# Variable_PWM.net
KiCad netlist of a schematic drawn in EAGLE
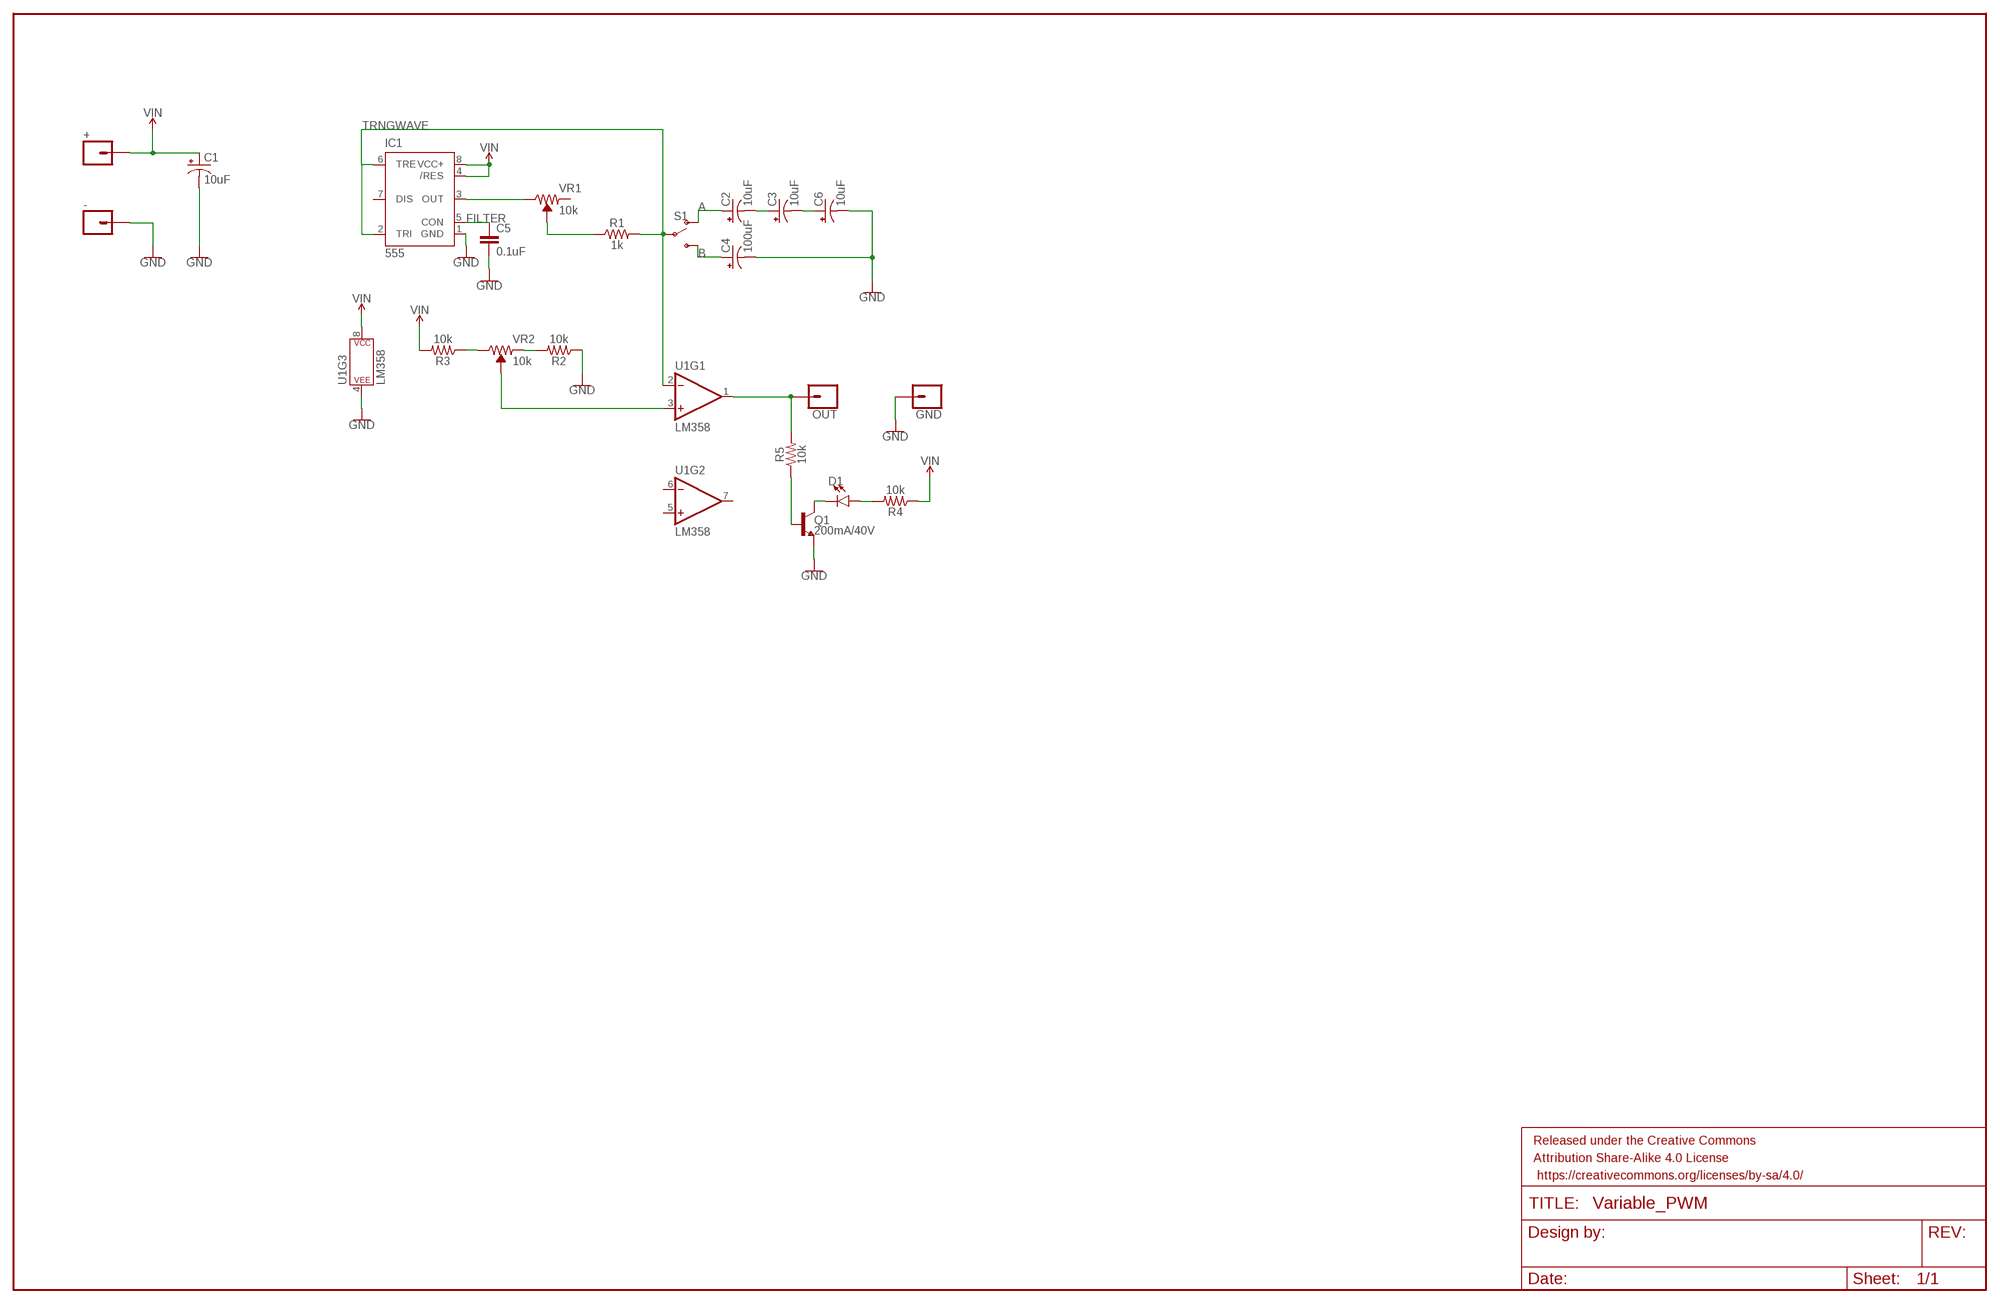
[diagram p0: schematic, sheet 1]

(export (version "E")
  (design (tool "Eeschema 10.0.6"))
  (components
    (comp (ref "+")
      (value "CONN_01")
      (footprint "eagle-import:1X01")
      (libsource (lib "eagle-import") (part "CONN_01"))
    )
    (comp (ref "-")
      (value "CONN_01")
      (footprint "eagle-import:1X01")
      (libsource (lib "eagle-import") (part "CONN_01"))
    )
    (comp (ref "C1")
      (value "10uF")
      (footprint "eagle-import:CPOL-RADIAL-2.5MM-5MM")
      (libsource (lib "eagle-import") (part "10UF-POLAR-RADIAL-2.5MM-25V-20%"))
    )
    (comp (ref "C2")
      (value "10uF")
      (footprint "eagle-import:CPOL-RADIAL-2.5MM-5MM")
      (libsource (lib "eagle-import") (part "10UF-POLAR-RADIAL-2.5MM-25V-20%"))
    )
    (comp (ref "C3")
      (value "10uF")
      (footprint "eagle-import:CPOL-RADIAL-2.5MM-5MM")
      (libsource (lib "eagle-import") (part "10UF-POLAR-RADIAL-2.5MM-25V-20%"))
    )
    (comp (ref "C4")
      (value "100uF")
      (footprint "eagle-import:CPOL-RADIAL-2.5MM-6.5MM")
      (libsource (lib "eagle-import") (part "100UF-POLAR-RADIAL-2.5MM-25V-20%"))
    )
    (comp (ref "C5")
      (value "0.1uF")
      (footprint "eagle-import:CAP-PTH-SMALL-KIT")
      (libsource (lib "eagle-import") (part "0.1UF-KIT-EZ-50V-20%"))
    )
    (comp (ref "C6")
      (value "10uF")
      (footprint "eagle-import:CPOL-RADIAL-2.5MM-5MM")
      (libsource (lib "eagle-import") (part "10UF-POLAR-RADIAL-2.5MM-25V-20%"))
    )
    (comp (ref "D1")
      (value "LED5MM")
      (footprint "eagle-import:LED_5MM")
      (libsource (lib "eagle-import") (part "LED5MM"))
    )
    (comp (ref "FRAME1")
      (value "FRAME-LEDGERNO_FOOTPRINT")
      (footprint "eagle-import:DUMMY")
      (libsource (lib "eagle-import") (part "FRAME-LEDGERNO_FOOTPRINT"))
    )
    (comp (ref "GND")
      (value "CONN_01")
      (footprint "eagle-import:1X01")
      (libsource (lib "eagle-import") (part "CONN_01"))
    )
    (comp (ref "IC1")
      (value "555")
      (footprint "eagle-import:DIP08")
      (libsource (lib "eagle-import") (part "555P"))
    )
    (comp (ref "OUT")
      (value "CONN_01")
      (footprint "eagle-import:1X01")
      (libsource (lib "eagle-import") (part "CONN_01"))
    )
    (comp (ref "Q1")
      (value "200mA/40V")
      (footprint "eagle-import:TO-92")
      (libsource (lib "eagle-import") (part "TRANS_NPN-2N3904"))
    )
    (comp (ref "R1")
      (value "1k")
      (footprint "eagle-import:AXIAL-0.3")
      (libsource (lib "eagle-import") (part "1KOHM-HORIZ-1/4W-1%"))
    )
    (comp (ref "R2")
      (value "10k")
      (footprint "eagle-import:AXIAL-0.3")
      (libsource (lib "eagle-import") (part "10KOHM-HORIZ-1/4W-1%"))
    )
    (comp (ref "R3")
      (value "10k")
      (footprint "eagle-import:AXIAL-0.3")
      (libsource (lib "eagle-import") (part "10KOHM-HORIZ-1/4W-1%"))
    )
    (comp (ref "R4")
      (value "10k")
      (footprint "eagle-import:AXIAL-0.3")
      (libsource (lib "eagle-import") (part "10KOHM-HORIZ-1/4W-1%"))
    )
    (comp (ref "R5")
      (value "10k")
      (footprint "eagle-import:AXIAL-0.3")
      (libsource (lib "eagle-import") (part "10KOHM-HORIZ-1/4W-1%"))
    )
    (comp (ref "S1")
      (value "SWITCH-SPDT-PTH-11.6X4.0MM")
      (footprint "eagle-import:SWITCH_SPDT_PTH_11.6X4.0MM")
      (libsource (lib "eagle-import") (part "SWITCH-SPDT-PTH-11.6X4.0MM"))
    )
    (comp (ref "U1")
      (value "LM358")
      (footprint "eagle-import:DIP08")
      (libsource (lib "eagle-import") (part "LM358"))
    )
    (comp (ref "VR1")
      (value "10k")
      (footprint "eagle-import:TRIMPOT-PTH-3386U")
      (libsource (lib "eagle-import") (part "TRIMPOT-PTH-10MM-KNOB-1/2W-10%"))
    )
    (comp (ref "VR2")
      (value "10k")
      (footprint "eagle-import:TRIMPOT-PTH-3386U")
      (libsource (lib "eagle-import") (part "TRIMPOT-PTH-10MM-KNOB-1/2W-10%"))
    )
  )
  (nets
    (net (code "1") (name "/A") (class "Default")
      (node (ref "C2") (pin "1") (pinfunction "+_1") (pintype "passive"))
      (node (ref "S1") (pin "1") (pinfunction "O_1") (pintype "passive"))
    )
    (net (code "2") (name "/B") (class "Default")
      (node (ref "C4") (pin "1") (pinfunction "+_1") (pintype "passive"))
      (node (ref "S1") (pin "3") (pinfunction "S_3") (pintype "passive"))
    )
    (net (code "3") (name "/FILTER") (class "Default")
      (node (ref "C5") (pin "1") (pinfunction "1_1") (pintype "passive"))
      (node (ref "IC1") (pin "5") (pinfunction "CON_5") (pintype "input"))
    )
    (net (code "4") (name "/TRNGWAVE") (class "Default")
      (node (ref "IC1") (pin "2") (pinfunction "TRI_2") (pintype "input"))
      (node (ref "IC1") (pin "6") (pinfunction "TRE_6") (pintype "input"))
      (node (ref "R1") (pin "P$2") (pinfunction "2_P$2") (pintype "passive"))
      (node (ref "S1") (pin "2") (pinfunction "P_2") (pintype "passive"))
      (node (ref "U1") (pin "2") (pinfunction "-IN_2") (pintype "input"))
    )
    (net (code "5") (name "GND") (class "Default")
      (node (ref "-") (pin "1") (pinfunction "1_1") (pintype "passive"))
      (node (ref "C1") (pin "2") (pinfunction "-_2") (pintype "passive"))
      (node (ref "C4") (pin "2") (pinfunction "-_2") (pintype "passive"))
      (node (ref "C5") (pin "2") (pinfunction "2_2") (pintype "passive"))
      (node (ref "C6") (pin "2") (pinfunction "-_2") (pintype "passive"))
      (node (ref "GND") (pin "1") (pinfunction "1_1") (pintype "passive"))
      (node (ref "IC1") (pin "1") (pinfunction "GND_1") (pintype "power_in"))
      (node (ref "Q1") (pin "1") (pinfunction "E_1") (pintype "passive"))
      (node (ref "R2") (pin "P$1") (pinfunction "1_P$1") (pintype "passive"))
      (node (ref "U1") (pin "4") (pinfunction "P$V-_4") (pintype "bidirectional"))
    )
    (net (code "6") (name "Net-(C2--)") (class "Default")
      (node (ref "C2") (pin "2") (pinfunction "-_2") (pintype "passive"))
      (node (ref "C3") (pin "1") (pinfunction "+_1") (pintype "passive"))
    )
    (net (code "7") (name "Net-(C3--)") (class "Default")
      (node (ref "C3") (pin "2") (pinfunction "-_2") (pintype "passive"))
      (node (ref "C6") (pin "1") (pinfunction "+_1") (pintype "passive"))
    )
    (net (code "8") (name "Net-(D1-C)") (class "Default")
      (node (ref "D1") (pin "K") (pinfunction "C_K") (pintype "passive"))
      (node (ref "Q1") (pin "3") (pinfunction "C_3") (pintype "passive"))
    )
    (net (code "9") (name "Net-(IC1-OUT)") (class "Default")
      (node (ref "IC1") (pin "3") (pinfunction "OUT_3") (pintype "output"))
      (node (ref "VR1") (pin "3") (pinfunction "CW_3") (pintype "passive"))
    )
    (net (code "10") (name "Net-(Q1-B)") (class "Default")
      (node (ref "Q1") (pin "2") (pinfunction "B_2") (pintype "passive"))
      (node (ref "R5") (pin "P$1") (pinfunction "1_P$1") (pintype "passive"))
    )
    (net (code "11") (name "Net-(R1-1)") (class "Default")
      (node (ref "R1") (pin "P$1") (pinfunction "1_P$1") (pintype "passive"))
      (node (ref "VR1") (pin "2") (pinfunction "WIPER_2") (pintype "passive"))
    )
    (net (code "12") (name "Net-(R2-2)") (class "Default")
      (node (ref "R2") (pin "P$2") (pinfunction "2_P$2") (pintype "passive"))
      (node (ref "VR2") (pin "1") (pinfunction "CCW_1") (pintype "passive"))
    )
    (net (code "13") (name "Net-(R3-1)") (class "Default")
      (node (ref "R3") (pin "P$1") (pinfunction "1_P$1") (pintype "passive"))
      (node (ref "VR2") (pin "3") (pinfunction "CW_3") (pintype "passive"))
    )
    (net (code "14") (name "Net-(R4-2)") (class "Default")
      (node (ref "D1") (pin "A") (pinfunction "A_A") (pintype "passive"))
      (node (ref "R4") (pin "P$2") (pinfunction "2_P$2") (pintype "passive"))
    )
    (net (code "15") (name "Net-(R5-2)") (class "Default")
      (node (ref "OUT") (pin "1") (pinfunction "1_1") (pintype "passive"))
      (node (ref "R5") (pin "P$2") (pinfunction "2_P$2") (pintype "passive"))
      (node (ref "U1") (pin "1") (pinfunction "OUT_1") (pintype "output"))
    )
    (net (code "16") (name "Net-(U1A-+IN)") (class "Default")
      (node (ref "U1") (pin "3") (pinfunction "+IN_3") (pintype "input"))
      (node (ref "VR2") (pin "2") (pinfunction "WIPER_2") (pintype "passive"))
    )
    (net (code "17") (name "VIN") (class "Default")
      (node (ref "+") (pin "1") (pinfunction "1_1") (pintype "passive"))
      (node (ref "C1") (pin "1") (pinfunction "+_1") (pintype "passive"))
      (node (ref "IC1") (pin "4") (pinfunction "/RES_4") (pintype "input"))
      (node (ref "IC1") (pin "8") (pinfunction "VCC+_8") (pintype "power_in"))
      (node (ref "R3") (pin "P$2") (pinfunction "2_P$2") (pintype "passive"))
      (node (ref "R4") (pin "P$1") (pinfunction "1_P$1") (pintype "passive"))
      (node (ref "U1") (pin "8") (pinfunction "P$V+_8") (pintype "bidirectional"))
    )
    (net (code "18") (name "unconnected-(IC1-DIS-Pad7)") (class "Default")
      (node (ref "IC1") (pin "7") (pinfunction "DIS_7") (pintype "input"))
    )
    (net (code "19") (name "unconnected-(U1B-+IN-Pad5)") (class "Default")
      (node (ref "U1") (pin "5") (pinfunction "+IN_5") (pintype "input"))
    )
    (net (code "20") (name "unconnected-(U1B--IN-Pad6)") (class "Default")
      (node (ref "U1") (pin "6") (pinfunction "-IN_6") (pintype "input"))
    )
    (net (code "21") (name "unconnected-(U1B-OUT-Pad7)") (class "Default")
      (node (ref "U1") (pin "7") (pinfunction "OUT_7") (pintype "output"))
    )
    (net (code "22") (name "unconnected-(VR1-CCW-Pad1)") (class "Default")
      (node (ref "VR1") (pin "1") (pinfunction "CCW_1") (pintype "passive"))
    )
  )
)
